# tunable_laser_controller.net
KiCad netlist of a schematic drawn in EAGLE
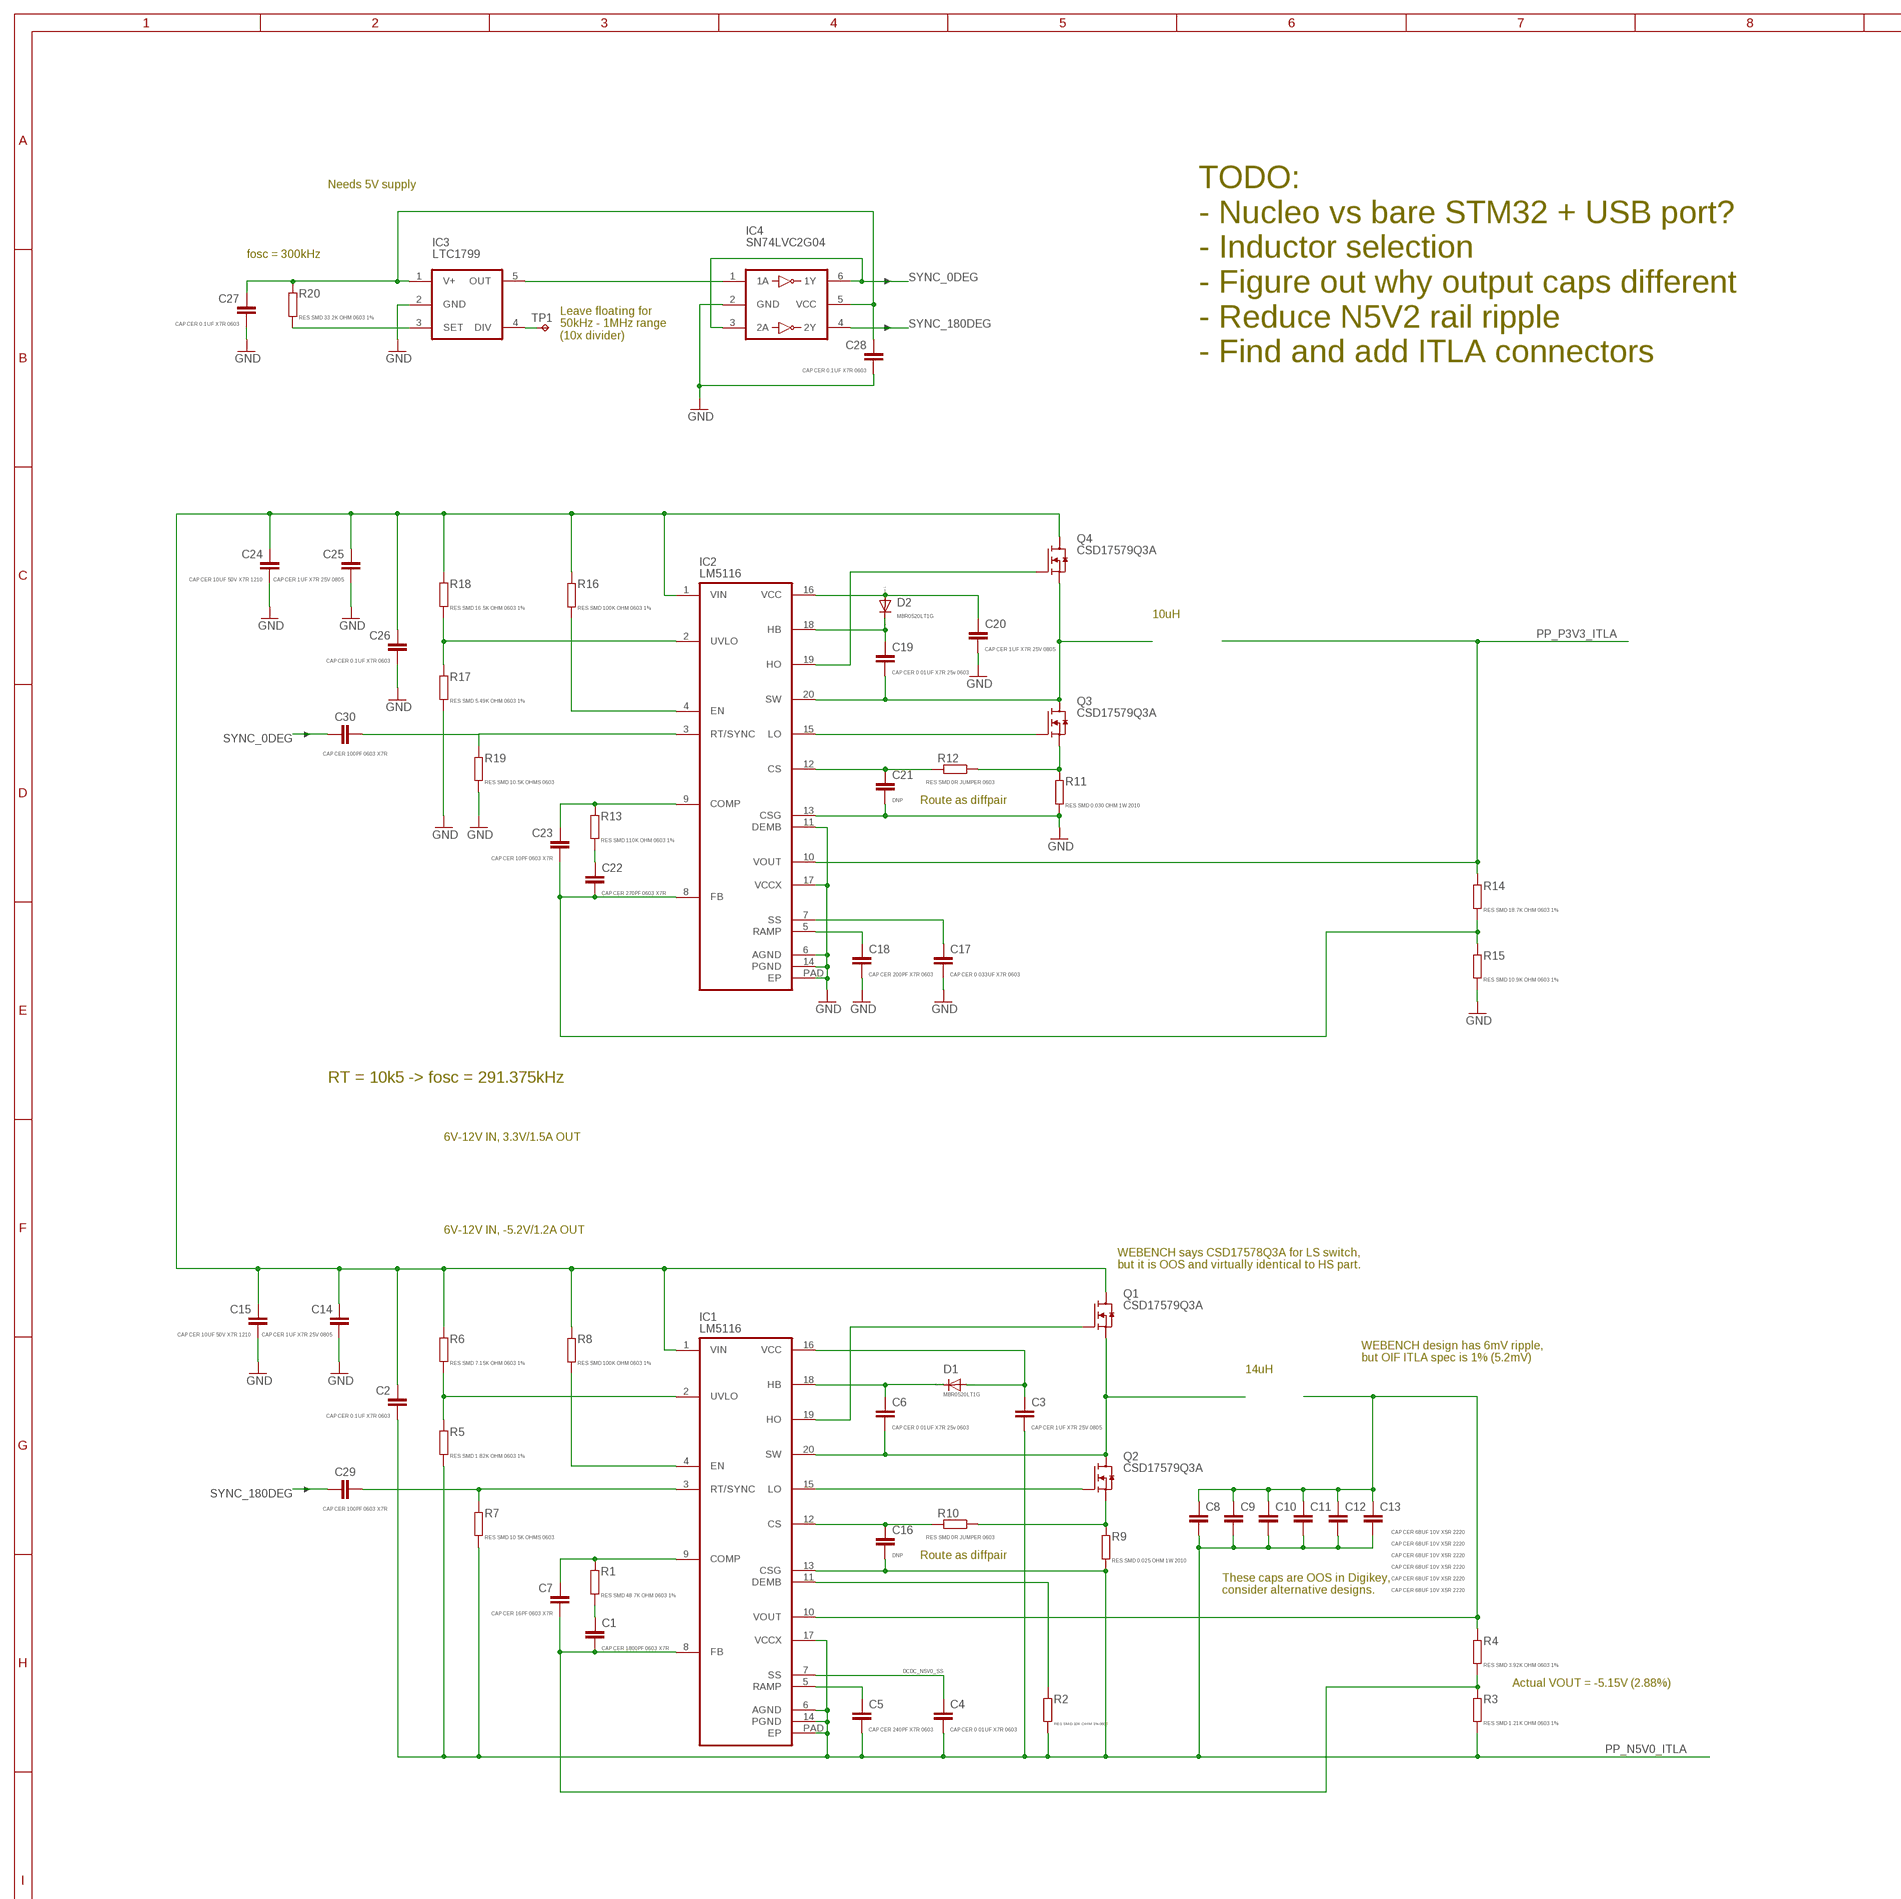
[diagram p0: schematic, sheet 1, part 1 of 2]
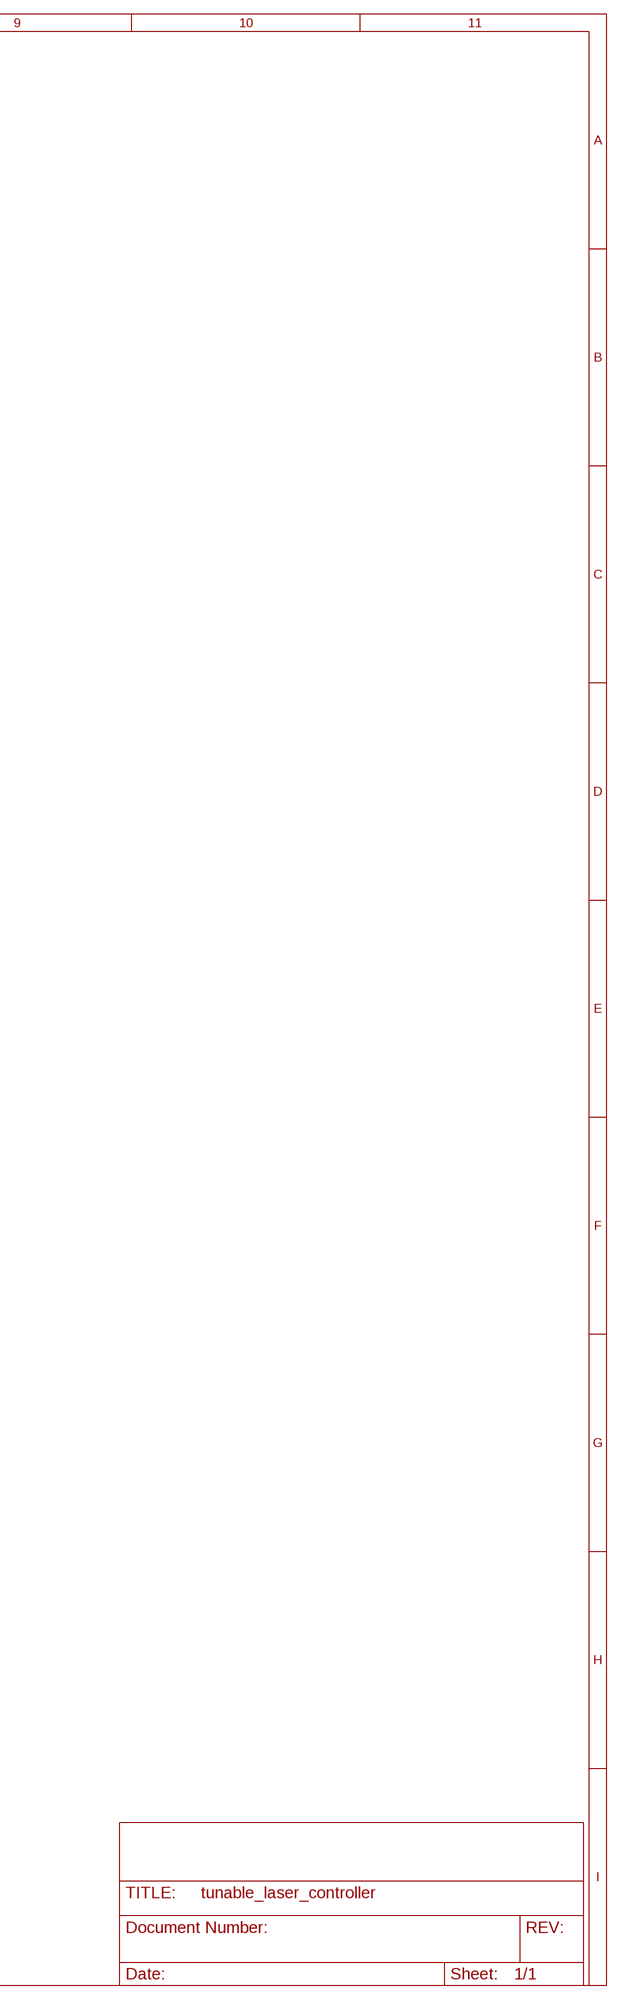
[diagram p1: schematic, sheet 1, part 2 of 2]

(export (version "E")
  (design (tool "Eeschema 10.0.6"))
  (components
    (comp (ref "C1")
      (value "CAP CER 1800PF 0603 X7R")
      (footprint "eagle-import:C0603")
      (libsource (lib "eagle-import") (part "C-EUC0603"))
    )
    (comp (ref "C2")
      (value "CAP CER 0.1UF X7R 0603")
      (footprint "eagle-import:C0603")
      (libsource (lib "eagle-import") (part "C-EUC0603"))
    )
    (comp (ref "C3")
      (value "CAP CER 1UF X7R 25V 0805")
      (footprint "eagle-import:C0805")
      (libsource (lib "eagle-import") (part "C-EUC0805"))
    )
    (comp (ref "C4")
      (value "CAP CER 0.01UF X7R 0603")
      (footprint "eagle-import:C0603")
      (libsource (lib "eagle-import") (part "C-EUC0603"))
    )
    (comp (ref "C5")
      (value "CAP CER 240PF X7R 0603")
      (footprint "eagle-import:C0603")
      (libsource (lib "eagle-import") (part "C-EUC0603"))
    )
    (comp (ref "C6")
      (value "CAP CER 0.01UF X7R 25v 0603")
      (footprint "eagle-import:C0603")
      (libsource (lib "eagle-import") (part "C-EUC0603"))
    )
    (comp (ref "C7")
      (value "CAP CER 16PF 0603 X7R")
      (footprint "eagle-import:C0603")
      (libsource (lib "eagle-import") (part "C-EUC0603"))
    )
    (comp (ref "C8")
      (value "CAP CER 68UF 10V X5R 2220")
      (footprint "eagle-import:C2220K")
      (libsource (lib "eagle-import") (part "C-EUC2220K"))
    )
    (comp (ref "C9")
      (value "CAP CER 68UF 10V X5R 2220")
      (footprint "eagle-import:C2220K")
      (libsource (lib "eagle-import") (part "C-EUC2220K"))
    )
    (comp (ref "C10")
      (value "CAP CER 68UF 10V X5R 2220")
      (footprint "eagle-import:C2220K")
      (libsource (lib "eagle-import") (part "C-EUC2220K"))
    )
    (comp (ref "C11")
      (value "CAP CER 68UF 10V X5R 2220")
      (footprint "eagle-import:C2220K")
      (libsource (lib "eagle-import") (part "C-EUC2220K"))
    )
    (comp (ref "C12")
      (value "CAP CER 68UF 10V X5R 2220")
      (footprint "eagle-import:C2220K")
      (libsource (lib "eagle-import") (part "C-EUC2220K"))
    )
    (comp (ref "C13")
      (value "CAP CER 68UF 10V X5R 2220")
      (footprint "eagle-import:C2220K")
      (libsource (lib "eagle-import") (part "C-EUC2220K"))
    )
    (comp (ref "C14")
      (value "CAP CER 1UF X7R 25V 0805")
      (footprint "eagle-import:C0805")
      (libsource (lib "eagle-import") (part "C-EUC0805"))
    )
    (comp (ref "C15")
      (value "CAP CER 10UF 50V X7R 1210")
      (footprint "eagle-import:C1210")
      (libsource (lib "eagle-import") (part "C-EUC1210"))
    )
    (comp (ref "C16")
      (value "DNP")
      (footprint "eagle-import:C0603")
      (libsource (lib "eagle-import") (part "C-EUC0603"))
    )
    (comp (ref "C17")
      (value "CAP CER 0.033UF X7R 0603")
      (footprint "eagle-import:C0603")
      (libsource (lib "eagle-import") (part "C-EUC0603"))
    )
    (comp (ref "C18")
      (value "CAP CER 200PF X7R 0603")
      (footprint "eagle-import:C0603")
      (libsource (lib "eagle-import") (part "C-EUC0603"))
    )
    (comp (ref "C19")
      (value "CAP CER 0.01UF X7R 25v 0603")
      (footprint "eagle-import:C0603")
      (libsource (lib "eagle-import") (part "C-EUC0603"))
    )
    (comp (ref "C20")
      (value "CAP CER 1UF X7R 25V 0805")
      (footprint "eagle-import:C0805")
      (libsource (lib "eagle-import") (part "C-EUC0805"))
    )
    (comp (ref "C21")
      (value "DNP")
      (footprint "eagle-import:C0603")
      (libsource (lib "eagle-import") (part "C-EUC0603"))
    )
    (comp (ref "C22")
      (value "CAP CER 270PF 0603 X7R")
      (footprint "eagle-import:C0603")
      (libsource (lib "eagle-import") (part "C-EUC0603"))
    )
    (comp (ref "C23")
      (value "CAP CER 10PF 0603 X7R")
      (footprint "eagle-import:C0603")
      (libsource (lib "eagle-import") (part "C-EUC0603"))
    )
    (comp (ref "C24")
      (value "CAP CER 10UF 50V X7R 1210")
      (footprint "eagle-import:C1210")
      (libsource (lib "eagle-import") (part "C-EUC1210"))
    )
    (comp (ref "C25")
      (value "CAP CER 1UF X7R 25V 0805")
      (footprint "eagle-import:C0805")
      (libsource (lib "eagle-import") (part "C-EUC0805"))
    )
    (comp (ref "C26")
      (value "CAP CER 0.1UF X7R 0603")
      (footprint "eagle-import:C0603")
      (libsource (lib "eagle-import") (part "C-EUC0603"))
    )
    (comp (ref "C27")
      (value "CAP CER 0.1UF X7R 0603")
      (footprint "eagle-import:C0603")
      (libsource (lib "eagle-import") (part "C-EUC0603"))
    )
    (comp (ref "C28")
      (value "CAP CER 0.1UF X7R 0603")
      (footprint "eagle-import:C0603")
      (libsource (lib "eagle-import") (part "C-EUC0603"))
    )
    (comp (ref "C29")
      (value "CAP CER 100PF 0603 X7R")
      (footprint "eagle-import:C0603")
      (libsource (lib "eagle-import") (part "C-EUC0603"))
    )
    (comp (ref "C30")
      (value "CAP CER 100PF 0603 X7R")
      (footprint "eagle-import:C0603")
      (libsource (lib "eagle-import") (part "C-EUC0603"))
    )
    (comp (ref "D1")
      (value "MBR0520LT1G")
      (footprint "eagle-import:SOD-123_MINI-SMA")
      (libsource (lib "eagle-import") (part "CGRM400-G7"))
    )
    (comp (ref "D2")
      (value "MBR0520LT1G")
      (footprint "eagle-import:SOD-123_MINI-SMA")
      (libsource (lib "eagle-import") (part "CGRM400-G7"))
    )
    (comp (ref "IC1")
      (value "LM5116")
      (footprint "eagle-import:TSSOP20-PAD")
      (libsource (lib "eagle-import") (part "LM5116"))
    )
    (comp (ref "IC2")
      (value "LM5116")
      (footprint "eagle-import:TSSOP20-PAD")
      (libsource (lib "eagle-import") (part "LM5116"))
    )
    (comp (ref "IC3")
      (value "LTC1799")
      (footprint "eagle-import:SOT23-5L")
      (libsource (lib "eagle-import") (part "LTC1799"))
    )
    (comp (ref "IC4")
      (value "SN74LVC2G04")
      (footprint "eagle-import:SOT23-6L")
      (libsource (lib "eagle-import") (part "SN74LVC2G04"))
    )
    (comp (ref "Q1")
      (value "CSD17579Q3A")
      (footprint "eagle-import:8VSON")
      (libsource (lib "eagle-import") (part "CSD17579Q3A"))
    )
    (comp (ref "Q2")
      (value "CSD17579Q3A")
      (footprint "eagle-import:8VSON")
      (libsource (lib "eagle-import") (part "CSD17579Q3A"))
    )
    (comp (ref "Q3")
      (value "CSD17579Q3A")
      (footprint "eagle-import:8VSON")
      (libsource (lib "eagle-import") (part "CSD17579Q3A"))
    )
    (comp (ref "Q4")
      (value "CSD17579Q3A")
      (footprint "eagle-import:8VSON")
      (libsource (lib "eagle-import") (part "CSD17579Q3A"))
    )
    (comp (ref "R1")
      (value "RES SMD 48.7K OHM 0603 1%")
      (footprint "eagle-import:R0603")
      (libsource (lib "eagle-import") (part "R-EU_R0603"))
    )
    (comp (ref "R2")
      (value "RES SMD 10K OHM 1% 0603")
      (footprint "eagle-import:R0603")
      (libsource (lib "eagle-import") (part "R-EU_R0603"))
    )
    (comp (ref "R3")
      (value "RES SMD 1.21K OHM 0603 1%")
      (footprint "eagle-import:R0603")
      (libsource (lib "eagle-import") (part "R-EU_R0603"))
    )
    (comp (ref "R4")
      (value "RES SMD 3.92K OHM 0603 1%")
      (footprint "eagle-import:R0603")
      (libsource (lib "eagle-import") (part "R-EU_R0603"))
    )
    (comp (ref "R5")
      (value "RES SMD 1.82K OHM 0603 1%")
      (footprint "eagle-import:R0603")
      (libsource (lib "eagle-import") (part "R-EU_R0603"))
    )
    (comp (ref "R6")
      (value "RES SMD 7.15K OHM 0603 1%")
      (footprint "eagle-import:R0603")
      (libsource (lib "eagle-import") (part "R-EU_R0603"))
    )
    (comp (ref "R7")
      (value "RES SMD 10.5K OHMS 0603")
      (footprint "eagle-import:R0603")
      (libsource (lib "eagle-import") (part "R-EU_R0603"))
    )
    (comp (ref "R8")
      (value "RES SMD 100K OHM 0603 1%")
      (footprint "eagle-import:R0603")
      (libsource (lib "eagle-import") (part "R-EU_R0603"))
    )
    (comp (ref "R9")
      (value "RES SMD 0.025 OHM 1W 2010")
      (footprint "eagle-import:R1210")
      (libsource (lib "eagle-import") (part "R-EU_R1210"))
    )
    (comp (ref "R10")
      (value "RES SMD 0R JUMPER 0603")
      (footprint "eagle-import:R0603")
      (libsource (lib "eagle-import") (part "R-EU_R0603"))
    )
    (comp (ref "R11")
      (value "RES SMD 0.030 OHM 1W 2010")
      (footprint "eagle-import:R1210")
      (libsource (lib "eagle-import") (part "R-EU_R1210"))
    )
    (comp (ref "R12")
      (value "RES SMD 0R JUMPER 0603")
      (footprint "eagle-import:R0603")
      (libsource (lib "eagle-import") (part "R-EU_R0603"))
    )
    (comp (ref "R13")
      (value "RES SMD 110K OHM 0603 1%")
      (footprint "eagle-import:R0603")
      (libsource (lib "eagle-import") (part "R-EU_R0603"))
    )
    (comp (ref "R14")
      (value "RES SMD 18.7K OHM 0603 1%")
      (footprint "eagle-import:R0603")
      (libsource (lib "eagle-import") (part "R-EU_R0603"))
    )
    (comp (ref "R15")
      (value "RES SMD 10.9K OHM 0603 1%")
      (footprint "eagle-import:R0603")
      (libsource (lib "eagle-import") (part "R-EU_R0603"))
    )
    (comp (ref "R16")
      (value "RES SMD 100K OHM 0603 1%")
      (footprint "eagle-import:R0603")
      (libsource (lib "eagle-import") (part "R-EU_R0603"))
    )
    (comp (ref "R17")
      (value "RES SMD 5.49K OHM 0603 1%")
      (footprint "eagle-import:R0603")
      (libsource (lib "eagle-import") (part "R-EU_R0603"))
    )
    (comp (ref "R18")
      (value "RES SMD 16.5K OHM 0603 1%")
      (footprint "eagle-import:R0603")
      (libsource (lib "eagle-import") (part "R-EU_R0603"))
    )
    (comp (ref "R19")
      (value "RES SMD 10.5K OHMS 0603")
      (footprint "eagle-import:R0603")
      (libsource (lib "eagle-import") (part "R-EU_R0603"))
    )
    (comp (ref "R20")
      (value "RES SMD 33.2K OHM 0603 1%")
      (footprint "eagle-import:R0603")
      (libsource (lib "eagle-import") (part "R-EU_R0603"))
    )
    (comp (ref "TP1")
      (value "TPTP20R")
      (footprint "eagle-import:TP20R")
      (libsource (lib "eagle-import") (part "TPTP20R"))
    )
  )
  (nets
    (net (code "1") (name "/DCDC_N5V0_SS") (class "Default")
      (node (ref "C4") (pin "1") (pinfunction "1_1") (pintype "passive"))
      (node (ref "IC1") (pin "7") (pinfunction "SS_7") (pintype "passive"))
    )
    (net (code "2") (name "/PP_N5V0_ITLA") (class "Default")
      (node (ref "C10") (pin "2") (pinfunction "2_2") (pintype "passive"))
      (node (ref "C11") (pin "2") (pinfunction "2_2") (pintype "passive"))
      (node (ref "C12") (pin "2") (pinfunction "2_2") (pintype "passive"))
      (node (ref "C13") (pin "2") (pinfunction "2_2") (pintype "passive"))
      (node (ref "C16") (pin "2") (pinfunction "2_2") (pintype "passive"))
      (node (ref "C2") (pin "2") (pinfunction "2_2") (pintype "passive"))
      (node (ref "C3") (pin "2") (pinfunction "2_2") (pintype "passive"))
      (node (ref "C4") (pin "2") (pinfunction "2_2") (pintype "passive"))
      (node (ref "C5") (pin "2") (pinfunction "2_2") (pintype "passive"))
      (node (ref "C8") (pin "2") (pinfunction "2_2") (pintype "passive"))
      (node (ref "C9") (pin "2") (pinfunction "2_2") (pintype "passive"))
      (node (ref "IC1") (pin "13") (pinfunction "CSG_13") (pintype "input"))
      (node (ref "IC1") (pin "14") (pinfunction "PGND_14") (pintype "power_in"))
      (node (ref "IC1") (pin "17") (pinfunction "VCCX_17") (pintype "power_in"))
      (node (ref "IC1") (pin "6") (pinfunction "AGND_6") (pintype "passive"))
      (node (ref "IC1") (pin "PAD") (pinfunction "EP_PAD") (pintype "power_in"))
      (node (ref "R2") (pin "1") (pinfunction "1_1") (pintype "passive"))
      (node (ref "R3") (pin "1") (pinfunction "1_1") (pintype "passive"))
      (node (ref "R5") (pin "1") (pinfunction "1_1") (pintype "passive"))
      (node (ref "R7") (pin "1") (pinfunction "1_1") (pintype "passive"))
      (node (ref "R9") (pin "1") (pinfunction "1_1") (pintype "passive"))
    )
    (net (code "3") (name "/PP_P3V3_ITLA") (class "Default")
      (node (ref "IC2") (pin "10") (pinfunction "VOUT_10") (pintype "input"))
      (node (ref "R14") (pin "2") (pinfunction "2_2") (pintype "passive"))
    )
    (net (code "4") (name "/SYNC_0DEG") (class "Default")
      (node (ref "C30") (pin "1") (pinfunction "1_1") (pintype "passive"))
      (node (ref "IC4") (pin "3") (pinfunction "2A_3") (pintype "bidirectional"))
      (node (ref "IC4") (pin "6") (pinfunction "1Y_6") (pintype "bidirectional"))
    )
    (net (code "5") (name "/SYNC_180DEG") (class "Default")
      (node (ref "C29") (pin "1") (pinfunction "1_1") (pintype "passive"))
      (node (ref "IC4") (pin "4") (pinfunction "2Y_4") (pintype "bidirectional"))
    )
    (net (code "6") (name "GND") (class "Default")
      (node (ref "C14") (pin "2") (pinfunction "2_2") (pintype "passive"))
      (node (ref "C15") (pin "2") (pinfunction "2_2") (pintype "passive"))
      (node (ref "C17") (pin "2") (pinfunction "2_2") (pintype "passive"))
      (node (ref "C18") (pin "2") (pinfunction "2_2") (pintype "passive"))
      (node (ref "C20") (pin "2") (pinfunction "2_2") (pintype "passive"))
      (node (ref "C21") (pin "2") (pinfunction "2_2") (pintype "passive"))
      (node (ref "C24") (pin "2") (pinfunction "2_2") (pintype "passive"))
      (node (ref "C25") (pin "2") (pinfunction "2_2") (pintype "passive"))
      (node (ref "C26") (pin "2") (pinfunction "2_2") (pintype "passive"))
      (node (ref "C27") (pin "2") (pinfunction "2_2") (pintype "passive"))
      (node (ref "C28") (pin "2") (pinfunction "2_2") (pintype "passive"))
      (node (ref "IC2") (pin "11") (pinfunction "DEMB_11") (pintype "input"))
      (node (ref "IC2") (pin "13") (pinfunction "CSG_13") (pintype "input"))
      (node (ref "IC2") (pin "14") (pinfunction "PGND_14") (pintype "power_in"))
      (node (ref "IC2") (pin "17") (pinfunction "VCCX_17") (pintype "power_in"))
      (node (ref "IC2") (pin "6") (pinfunction "AGND_6") (pintype "passive"))
      (node (ref "IC2") (pin "PAD") (pinfunction "EP_PAD") (pintype "power_in"))
      (node (ref "IC3") (pin "2") (pinfunction "GND_2") (pintype "bidirectional"))
      (node (ref "IC4") (pin "2") (pinfunction "GND_2") (pintype "bidirectional"))
      (node (ref "R11") (pin "1") (pinfunction "1_1") (pintype "passive"))
      (node (ref "R15") (pin "1") (pinfunction "1_1") (pintype "passive"))
      (node (ref "R17") (pin "1") (pinfunction "1_1") (pintype "passive"))
      (node (ref "R19") (pin "1") (pinfunction "1_1") (pintype "passive"))
    )
    (net (code "7") (name "Net-(C1-Pad1)") (class "Default")
      (node (ref "C1") (pin "1") (pinfunction "1_1") (pintype "passive"))
      (node (ref "R1") (pin "1") (pinfunction "1_1") (pintype "passive"))
    )
    (net (code "8") (name "Net-(C22-Pad1)") (class "Default")
      (node (ref "C22") (pin "1") (pinfunction "1_1") (pintype "passive"))
      (node (ref "R13") (pin "1") (pinfunction "1_1") (pintype "passive"))
    )
    (net (code "9") (name "Net-(IC1-COMP)") (class "Default")
      (node (ref "C7") (pin "1") (pinfunction "1_1") (pintype "passive"))
      (node (ref "IC1") (pin "9") (pinfunction "COMP_9") (pintype "output"))
      (node (ref "R1") (pin "2") (pinfunction "2_2") (pintype "passive"))
    )
    (net (code "10") (name "Net-(IC1-CS)") (class "Default")
      (node (ref "C16") (pin "1") (pinfunction "1_1") (pintype "passive"))
      (node (ref "IC1") (pin "12") (pinfunction "CS_12") (pintype "input"))
      (node (ref "R10") (pin "2") (pinfunction "2_2") (pintype "passive"))
    )
    (net (code "11") (name "Net-(IC1-DEMB)") (class "Default")
      (node (ref "IC1") (pin "11") (pinfunction "DEMB_11") (pintype "input"))
      (node (ref "R2") (pin "2") (pinfunction "2_2") (pintype "passive"))
    )
    (net (code "12") (name "Net-(IC1-EN)") (class "Default")
      (node (ref "IC1") (pin "4") (pinfunction "EN_4") (pintype "input"))
      (node (ref "R8") (pin "2") (pinfunction "2_2") (pintype "passive"))
    )
    (net (code "13") (name "Net-(IC1-FB)") (class "Default")
      (node (ref "C1") (pin "2") (pinfunction "2_2") (pintype "passive"))
      (node (ref "C7") (pin "2") (pinfunction "2_2") (pintype "passive"))
      (node (ref "IC1") (pin "8") (pinfunction "FB_8") (pintype "input"))
      (node (ref "R3") (pin "2") (pinfunction "2_2") (pintype "passive"))
      (node (ref "R4") (pin "1") (pinfunction "1_1") (pintype "passive"))
    )
    (net (code "14") (name "Net-(IC1-HB)") (class "Default")
      (node (ref "C6") (pin "1") (pinfunction "1_1") (pintype "passive"))
      (node (ref "D1") (pin "C") (pinfunction "C_C") (pintype "passive"))
      (node (ref "IC1") (pin "18") (pinfunction "HB_18") (pintype "passive"))
    )
    (net (code "15") (name "Net-(IC1-HO)") (class "Default")
      (node (ref "IC1") (pin "19") (pinfunction "HO_19") (pintype "output"))
      (node (ref "Q1") (pin "4") (pinfunction "G_4") (pintype "passive"))
    )
    (net (code "16") (name "Net-(IC1-LO)") (class "Default")
      (node (ref "IC1") (pin "15") (pinfunction "LO_15") (pintype "output"))
      (node (ref "Q2") (pin "4") (pinfunction "G_4") (pintype "passive"))
    )
    (net (code "17") (name "Net-(IC1-RAMP)") (class "Default")
      (node (ref "C5") (pin "1") (pinfunction "1_1") (pintype "passive"))
      (node (ref "IC1") (pin "5") (pinfunction "RAMP_5") (pintype "passive"))
    )
    (net (code "18") (name "Net-(IC1-RT{slash}SYNC)") (class "Default")
      (node (ref "C29") (pin "2") (pinfunction "2_2") (pintype "passive"))
      (node (ref "IC1") (pin "3") (pinfunction "RT/SYNC_3") (pintype "passive"))
      (node (ref "R7") (pin "2") (pinfunction "2_2") (pintype "passive"))
    )
    (net (code "19") (name "Net-(IC1-SW)") (class "Default")
      (node (ref "C6") (pin "2") (pinfunction "2_2") (pintype "passive"))
      (node (ref "IC1") (pin "20") (pinfunction "SW_20") (pintype "passive"))
      (node (ref "Q1") (pin "1") (pinfunction "S_1") (pintype "passive"))
      (node (ref "Q1") (pin "2") (pinfunction "S_2") (pintype "passive"))
      (node (ref "Q1") (pin "3") (pinfunction "S_3") (pintype "passive"))
      (node (ref "Q2") (pin "5") (pinfunction "D_5") (pintype "passive"))
      (node (ref "Q2") (pin "6") (pinfunction "D_6") (pintype "passive"))
      (node (ref "Q2") (pin "7") (pinfunction "D_7") (pintype "passive"))
      (node (ref "Q2") (pin "8") (pinfunction "D_8") (pintype "passive"))
      (node (ref "Q2") (pin "9") (pinfunction "D_9") (pintype "passive"))
      (node (ref "Q2") (pin "V1") (pinfunction "D_V1") (pintype "passive"))
      (node (ref "Q2") (pin "V2") (pinfunction "D_V2") (pintype "passive"))
      (node (ref "Q2") (pin "V3") (pinfunction "D_V3") (pintype "passive"))
      (node (ref "Q2") (pin "V4") (pinfunction "D_V4") (pintype "passive"))
      (node (ref "Q2") (pin "V5") (pinfunction "D_V5") (pintype "passive"))
      (node (ref "Q2") (pin "V6") (pinfunction "D_V6") (pintype "passive"))
    )
    (net (code "20") (name "Net-(IC1-UVLO)") (class "Default")
      (node (ref "IC1") (pin "2") (pinfunction "UVLO_2") (pintype "passive"))
      (node (ref "R5") (pin "2") (pinfunction "2_2") (pintype "passive"))
      (node (ref "R6") (pin "1") (pinfunction "1_1") (pintype "passive"))
    )
    (net (code "21") (name "Net-(IC1-VCC)") (class "Default")
      (node (ref "C3") (pin "1") (pinfunction "1_1") (pintype "passive"))
      (node (ref "D1") (pin "A") (pinfunction "A_A") (pintype "passive"))
      (node (ref "IC1") (pin "16") (pinfunction "VCC_16") (pintype "power_in"))
    )
    (net (code "22") (name "Net-(IC1-VIN)") (class "Default")
      (node (ref "C14") (pin "1") (pinfunction "1_1") (pintype "passive"))
      (node (ref "C15") (pin "1") (pinfunction "1_1") (pintype "passive"))
      (node (ref "C2") (pin "1") (pinfunction "1_1") (pintype "passive"))
      (node (ref "C24") (pin "1") (pinfunction "1_1") (pintype "passive"))
      (node (ref "C25") (pin "1") (pinfunction "1_1") (pintype "passive"))
      (node (ref "C26") (pin "1") (pinfunction "1_1") (pintype "passive"))
      (node (ref "IC1") (pin "1") (pinfunction "VIN_1") (pintype "power_in"))
      (node (ref "IC2") (pin "1") (pinfunction "VIN_1") (pintype "power_in"))
      (node (ref "Q1") (pin "5") (pinfunction "D_5") (pintype "passive"))
      (node (ref "Q1") (pin "6") (pinfunction "D_6") (pintype "passive"))
      (node (ref "Q1") (pin "7") (pinfunction "D_7") (pintype "passive"))
      (node (ref "Q1") (pin "8") (pinfunction "D_8") (pintype "passive"))
      (node (ref "Q1") (pin "9") (pinfunction "D_9") (pintype "passive"))
      (node (ref "Q1") (pin "V1") (pinfunction "D_V1") (pintype "passive"))
      (node (ref "Q1") (pin "V2") (pinfunction "D_V2") (pintype "passive"))
      (node (ref "Q1") (pin "V3") (pinfunction "D_V3") (pintype "passive"))
      (node (ref "Q1") (pin "V4") (pinfunction "D_V4") (pintype "passive"))
      (node (ref "Q1") (pin "V5") (pinfunction "D_V5") (pintype "passive"))
      (node (ref "Q1") (pin "V6") (pinfunction "D_V6") (pintype "passive"))
      (node (ref "Q4") (pin "5") (pinfunction "D_5") (pintype "passive"))
      (node (ref "Q4") (pin "6") (pinfunction "D_6") (pintype "passive"))
      (node (ref "Q4") (pin "7") (pinfunction "D_7") (pintype "passive"))
      (node (ref "Q4") (pin "8") (pinfunction "D_8") (pintype "passive"))
      (node (ref "Q4") (pin "9") (pinfunction "D_9") (pintype "passive"))
      (node (ref "Q4") (pin "V1") (pinfunction "D_V1") (pintype "passive"))
      (node (ref "Q4") (pin "V2") (pinfunction "D_V2") (pintype "passive"))
      (node (ref "Q4") (pin "V3") (pinfunction "D_V3") (pintype "passive"))
      (node (ref "Q4") (pin "V4") (pinfunction "D_V4") (pintype "passive"))
      (node (ref "Q4") (pin "V5") (pinfunction "D_V5") (pintype "passive"))
      (node (ref "Q4") (pin "V6") (pinfunction "D_V6") (pintype "passive"))
      (node (ref "R16") (pin "1") (pinfunction "1_1") (pintype "passive"))
      (node (ref "R18") (pin "2") (pinfunction "2_2") (pintype "passive"))
      (node (ref "R6") (pin "2") (pinfunction "2_2") (pintype "passive"))
      (node (ref "R8") (pin "1") (pinfunction "1_1") (pintype "passive"))
    )
    (net (code "23") (name "Net-(IC1-VOUT)") (class "Default")
      (node (ref "C10") (pin "1") (pinfunction "1_1") (pintype "passive"))
      (node (ref "C11") (pin "1") (pinfunction "1_1") (pintype "passive"))
      (node (ref "C12") (pin "1") (pinfunction "1_1") (pintype "passive"))
      (node (ref "C13") (pin "1") (pinfunction "1_1") (pintype "passive"))
      (node (ref "C8") (pin "1") (pinfunction "1_1") (pintype "passive"))
      (node (ref "C9") (pin "1") (pinfunction "1_1") (pintype "passive"))
      (node (ref "IC1") (pin "10") (pinfunction "VOUT_10") (pintype "input"))
      (node (ref "R4") (pin "2") (pinfunction "2_2") (pintype "passive"))
    )
    (net (code "24") (name "Net-(IC2-COMP)") (class "Default")
      (node (ref "C23") (pin "1") (pinfunction "1_1") (pintype "passive"))
      (node (ref "IC2") (pin "9") (pinfunction "COMP_9") (pintype "output"))
      (node (ref "R13") (pin "2") (pinfunction "2_2") (pintype "passive"))
    )
    (net (code "25") (name "Net-(IC2-CS)") (class "Default")
      (node (ref "C21") (pin "1") (pinfunction "1_1") (pintype "passive"))
      (node (ref "IC2") (pin "12") (pinfunction "CS_12") (pintype "input"))
      (node (ref "R12") (pin "2") (pinfunction "2_2") (pintype "passive"))
    )
    (net (code "26") (name "Net-(IC2-EN)") (class "Default")
      (node (ref "IC2") (pin "4") (pinfunction "EN_4") (pintype "input"))
      (node (ref "R16") (pin "2") (pinfunction "2_2") (pintype "passive"))
    )
    (net (code "27") (name "Net-(IC2-FB)") (class "Default")
      (node (ref "C22") (pin "2") (pinfunction "2_2") (pintype "passive"))
      (node (ref "C23") (pin "2") (pinfunction "2_2") (pintype "passive"))
      (node (ref "IC2") (pin "8") (pinfunction "FB_8") (pintype "input"))
      (node (ref "R14") (pin "1") (pinfunction "1_1") (pintype "passive"))
      (node (ref "R15") (pin "2") (pinfunction "2_2") (pintype "passive"))
    )
    (net (code "28") (name "Net-(IC2-HB)") (class "Default")
      (node (ref "C19") (pin "1") (pinfunction "1_1") (pintype "passive"))
      (node (ref "D2") (pin "C") (pinfunction "C_C") (pintype "passive"))
      (node (ref "IC2") (pin "18") (pinfunction "HB_18") (pintype "passive"))
    )
    (net (code "29") (name "Net-(IC2-HO)") (class "Default")
      (node (ref "IC2") (pin "19") (pinfunction "HO_19") (pintype "output"))
      (node (ref "Q4") (pin "4") (pinfunction "G_4") (pintype "passive"))
    )
    (net (code "30") (name "Net-(IC2-LO)") (class "Default")
      (node (ref "IC2") (pin "15") (pinfunction "LO_15") (pintype "output"))
      (node (ref "Q3") (pin "4") (pinfunction "G_4") (pintype "passive"))
    )
    (net (code "31") (name "Net-(IC2-RAMP)") (class "Default")
      (node (ref "C18") (pin "1") (pinfunction "1_1") (pintype "passive"))
      (node (ref "IC2") (pin "5") (pinfunction "RAMP_5") (pintype "passive"))
    )
    (net (code "32") (name "Net-(IC2-RT{slash}SYNC)") (class "Default")
      (node (ref "C30") (pin "2") (pinfunction "2_2") (pintype "passive"))
      (node (ref "IC2") (pin "3") (pinfunction "RT/SYNC_3") (pintype "passive"))
      (node (ref "R19") (pin "2") (pinfunction "2_2") (pintype "passive"))
    )
    (net (code "33") (name "Net-(IC2-SS)") (class "Default")
      (node (ref "C17") (pin "1") (pinfunction "1_1") (pintype "passive"))
      (node (ref "IC2") (pin "7") (pinfunction "SS_7") (pintype "passive"))
    )
    (net (code "34") (name "Net-(IC2-SW)") (class "Default")
      (node (ref "C19") (pin "2") (pinfunction "2_2") (pintype "passive"))
      (node (ref "IC2") (pin "20") (pinfunction "SW_20") (pintype "passive"))
      (node (ref "Q3") (pin "5") (pinfunction "D_5") (pintype "passive"))
      (node (ref "Q3") (pin "6") (pinfunction "D_6") (pintype "passive"))
      (node (ref "Q3") (pin "7") (pinfunction "D_7") (pintype "passive"))
      (node (ref "Q3") (pin "8") (pinfunction "D_8") (pintype "passive"))
      (node (ref "Q3") (pin "9") (pinfunction "D_9") (pintype "passive"))
      (node (ref "Q3") (pin "V1") (pinfunction "D_V1") (pintype "passive"))
      (node (ref "Q3") (pin "V2") (pinfunction "D_V2") (pintype "passive"))
      (node (ref "Q3") (pin "V3") (pinfunction "D_V3") (pintype "passive"))
      (node (ref "Q3") (pin "V4") (pinfunction "D_V4") (pintype "passive"))
      (node (ref "Q3") (pin "V5") (pinfunction "D_V5") (pintype "passive"))
      (node (ref "Q3") (pin "V6") (pinfunction "D_V6") (pintype "passive"))
      (node (ref "Q4") (pin "1") (pinfunction "S_1") (pintype "passive"))
      (node (ref "Q4") (pin "2") (pinfunction "S_2") (pintype "passive"))
      (node (ref "Q4") (pin "3") (pinfunction "S_3") (pintype "passive"))
    )
    (net (code "35") (name "Net-(IC2-UVLO)") (class "Default")
      (node (ref "IC2") (pin "2") (pinfunction "UVLO_2") (pintype "passive"))
      (node (ref "R17") (pin "2") (pinfunction "2_2") (pintype "passive"))
      (node (ref "R18") (pin "1") (pinfunction "1_1") (pintype "passive"))
    )
    (net (code "36") (name "Net-(IC2-VCC)") (class "Default")
      (node (ref "C20") (pin "1") (pinfunction "1_1") (pintype "passive"))
      (node (ref "D2") (pin "A") (pinfunction "A_A") (pintype "passive"))
      (node (ref "IC2") (pin "16") (pinfunction "VCC_16") (pintype "power_in"))
    )
    (net (code "37") (name "Net-(IC3-DIV)") (class "Default")
      (node (ref "IC3") (pin "4") (pinfunction "DIV_4") (pintype "bidirectional"))
      (node (ref "TP1") (pin "TP") (pinfunction "TP_TP") (pintype "input"))
    )
    (net (code "38") (name "Net-(IC3-OUT)") (class "Default")
      (node (ref "IC3") (pin "5") (pinfunction "OUT_5") (pintype "bidirectional"))
      (node (ref "IC4") (pin "1") (pinfunction "1A_1") (pintype "bidirectional"))
    )
    (net (code "39") (name "Net-(IC3-SET)") (class "Default")
      (node (ref "IC3") (pin "3") (pinfunction "SET_3") (pintype "bidirectional"))
      (node (ref "R20") (pin "2") (pinfunction "2_2") (pintype "passive"))
    )
    (net (code "40") (name "Net-(IC3-V+)") (class "Default")
      (node (ref "C27") (pin "1") (pinfunction "1_1") (pintype "passive"))
      (node (ref "C28") (pin "1") (pinfunction "1_1") (pintype "passive"))
      (node (ref "IC3") (pin "1") (pinfunction "V+_1") (pintype "bidirectional"))
      (node (ref "IC4") (pin "5") (pinfunction "VCC_5") (pintype "bidirectional"))
      (node (ref "R20") (pin "1") (pinfunction "1_1") (pintype "passive"))
    )
    (net (code "41") (name "Net-(Q2-S-Pad1)") (class "Default")
      (node (ref "Q2") (pin "1") (pinfunction "S_1") (pintype "passive"))
      (node (ref "Q2") (pin "2") (pinfunction "S_2") (pintype "passive"))
      (node (ref "Q2") (pin "3") (pinfunction "S_3") (pintype "passive"))
      (node (ref "R10") (pin "1") (pinfunction "1_1") (pintype "passive"))
      (node (ref "R9") (pin "2") (pinfunction "2_2") (pintype "passive"))
    )
    (net (code "42") (name "Net-(Q3-S-Pad1)") (class "Default")
      (node (ref "Q3") (pin "1") (pinfunction "S_1") (pintype "passive"))
      (node (ref "Q3") (pin "2") (pinfunction "S_2") (pintype "passive"))
      (node (ref "Q3") (pin "3") (pinfunction "S_3") (pintype "passive"))
      (node (ref "R11") (pin "2") (pinfunction "2_2") (pintype "passive"))
      (node (ref "R12") (pin "1") (pinfunction "1_1") (pintype "passive"))
    )
  )
)
